# BendSensor.net
KiCad netlist of a schematic drawn in EAGLE
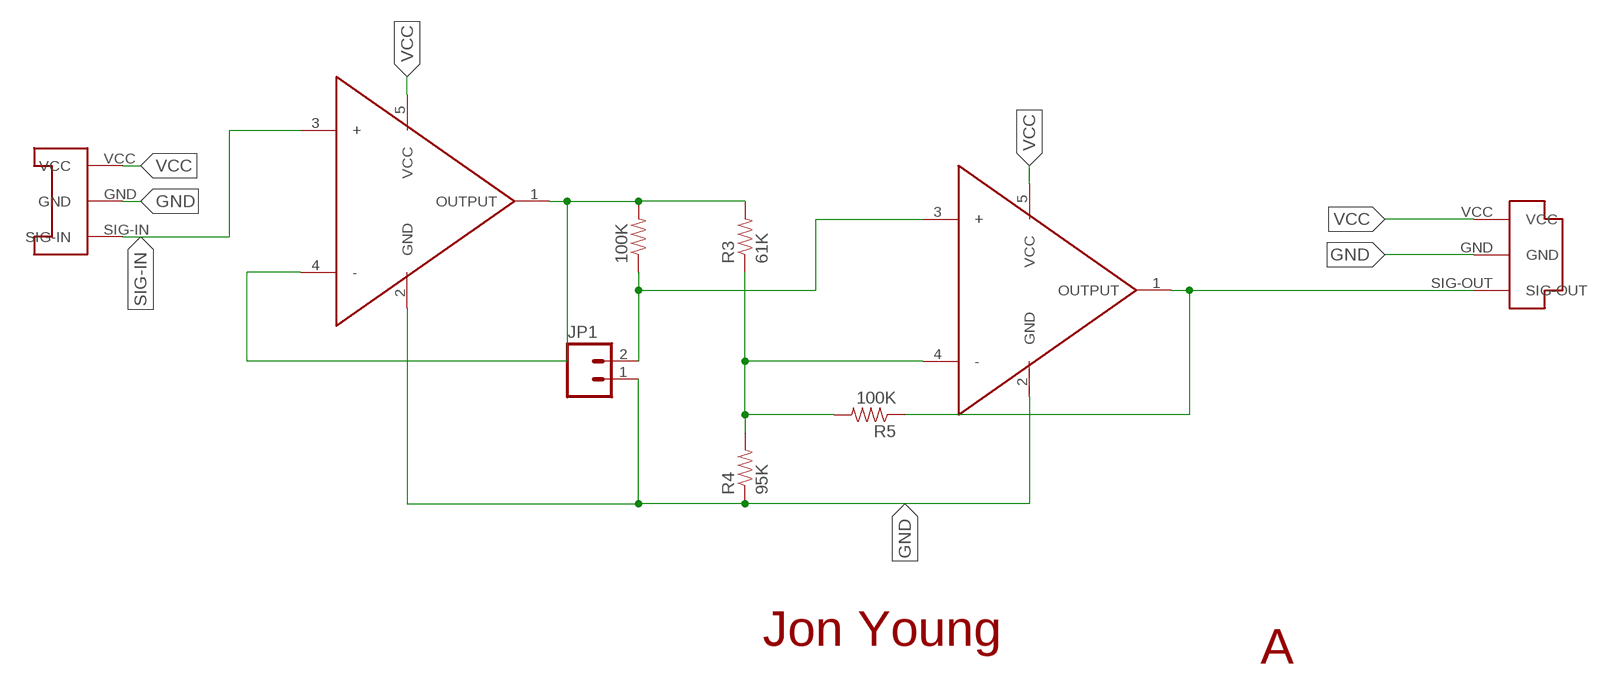
[diagram p0: schematic, sheet 1]

(export (version "E")
  (design (tool "Eeschema 10.0.6"))
  (components
    (comp (ref "100K")
      (value "RESISTOR0603")
      (footprint "eagle-import:0603-RES")
      (libsource (lib "eagle-import") (part "RESISTOR0603"))
    )
    (comp (ref "JP1")
      (value "M02PTH3")
      (footprint "eagle-import:1X02_LONGPADS")
      (libsource (lib "eagle-import") (part "M02PTH3"))
    )
    (comp (ref "R3")
      (value "61K")
      (footprint "eagle-import:0603-RES")
      (libsource (lib "eagle-import") (part "RESISTOR0603"))
    )
    (comp (ref "R4")
      (value "95K")
      (footprint "eagle-import:0603-RES")
      (libsource (lib "eagle-import") (part "RESISTOR0603"))
    )
    (comp (ref "R5")
      (value "100K")
      (footprint "eagle-import:0603-RES")
      (libsource (lib "eagle-import") (part "RESISTOR0603"))
    )
    (comp (ref "U$1")
      (value "CONN-PLUG-3POS-3MM")
      (footprint "eagle-import:PLUG-3POS-3MM-SMD")
      (libsource (lib "eagle-import") (part "CONN-PLUG-3POS-3MM"))
    )
    (comp (ref "U$2")
      (value "CONN-SOCKET-3POS-3MM")
      (footprint "eagle-import:SOCKET-3POS-3MM-SMD")
      (libsource (lib "eagle-import") (part "CONN-SOCKET-3POS-3MM"))
    )
    (comp (ref "U$3")
      (value "OPAMP-MCP6001SOT23-5")
      (footprint "eagle-import:SOT23-5")
      (libsource (lib "eagle-import") (part "OPAMP-MCP6001SOT23-5"))
    )
    (comp (ref "U$4")
      (value "OPAMP-MCP6001SOT23-5")
      (footprint "eagle-import:SOT23-5")
      (libsource (lib "eagle-import") (part "OPAMP-MCP6001SOT23-5"))
    )
  )
  (nets
    (net (code "1") (name "GND") (class "Default")
      (node (ref "JP1") (pin "1") (pinfunction "1_1") (pintype "passive"))
      (node (ref "R4") (pin "1") (pinfunction "1_1") (pintype "passive"))
      (node (ref "U$1") (pin "GND") (pinfunction "GND_GND") (pintype "power_in"))
      (node (ref "U$2") (pin "GND") (pinfunction "GND_GND") (pintype "power_in"))
      (node (ref "U$3") (pin "2") (pinfunction "GND_2") (pintype "power_in"))
      (node (ref "U$4") (pin "2") (pinfunction "GND_2") (pintype "power_in"))
    )
    (net (code "2") (name "Net-(U$3--)") (class "Default")
      (node (ref "100K") (pin "2") (pinfunction "2_2") (pintype "passive"))
      (node (ref "R3") (pin "2") (pinfunction "2_2") (pintype "passive"))
      (node (ref "U$3") (pin "1") (pinfunction "OUTPUT_1") (pintype "output"))
      (node (ref "U$3") (pin "4") (pinfunction "-_4") (pintype "input"))
    )
    (net (code "3") (name "Net-(U$4-+)") (class "Default")
      (node (ref "100K") (pin "1") (pinfunction "1_1") (pintype "passive"))
      (node (ref "JP1") (pin "2") (pinfunction "2_2") (pintype "passive"))
      (node (ref "U$4") (pin "3") (pinfunction "+_3") (pintype "input"))
    )
    (net (code "4") (name "Net-(U$4--)") (class "Default")
      (node (ref "R3") (pin "1") (pinfunction "1_1") (pintype "passive"))
      (node (ref "R4") (pin "2") (pinfunction "2_2") (pintype "passive"))
      (node (ref "R5") (pin "2") (pinfunction "2_2") (pintype "passive"))
      (node (ref "U$4") (pin "4") (pinfunction "-_4") (pintype "input"))
    )
    (net (code "5") (name "Net-(U$4-OUTPUT)") (class "Default")
      (node (ref "R5") (pin "1") (pinfunction "1_1") (pintype "passive"))
      (node (ref "U$1") (pin "SIG-OUT") (pinfunction "SIG-OUT_SIG-OUT") (pintype "bidirectional"))
      (node (ref "U$4") (pin "1") (pinfunction "OUTPUT_1") (pintype "output"))
    )
    (net (code "6") (name "SIG-IN") (class "Default")
      (node (ref "U$2") (pin "SIG-IN") (pinfunction "SIG-IN_SIG-IN") (pintype "bidirectional"))
      (node (ref "U$3") (pin "3") (pinfunction "+_3") (pintype "input"))
    )
    (net (code "7") (name "VCC") (class "Default")
      (node (ref "U$1") (pin "VCC") (pinfunction "VCC_VCC") (pintype "power_in"))
      (node (ref "U$2") (pin "VCC") (pinfunction "VCC_VCC") (pintype "power_in"))
      (node (ref "U$3") (pin "5") (pinfunction "VCC_5") (pintype "power_in"))
      (node (ref "U$4") (pin "5") (pinfunction "VCC_5") (pintype "power_in"))
    )
  )
)
